# H-mostik2.net
KiCad netlist of a schematic drawn in Altium Designer
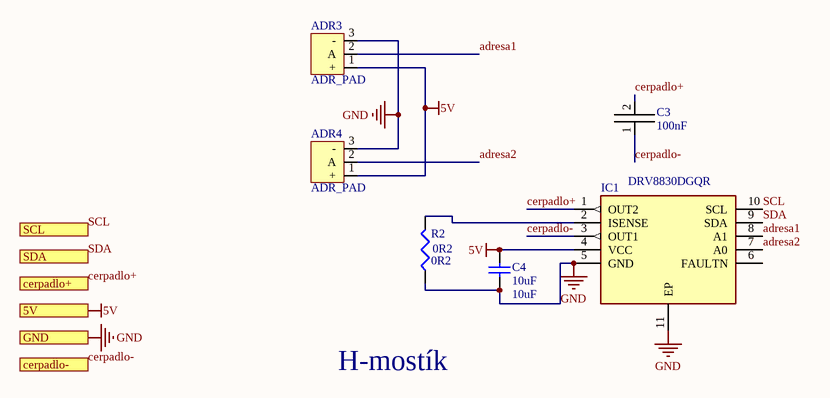
[diagram p0: H-mostik2.SchDoc]

(export (version "E")
  (design (tool "Eeschema 10.0.6"))
  (components
    (comp (ref "ADR3")
      (value "ADR_PAD")
      (footprint "SOLDER_PAD")
      (description "ADR PAD 3 PIN")
      (libsource (lib "SCH_Aquatec") (part "ADR_PAD"))
    )
    (comp (ref "ADR4")
      (value "ADR_PAD")
      (footprint "SOLDER_PAD")
      (description "ADR PAD 3 PIN")
      (libsource (lib "SCH_Aquatec") (part "ADR_PAD"))
    )
    (comp (ref "C3") (value "100nF") (footprint "Capacitor") (libsource (lib "SchematicLib_JP") (part "Cap")))
    (comp (ref "C4")
      (value "10uF")
      (footprint "C2512")
      (description "Capacitor (Semiconductor SIM Model)")
      (fields (field (name "ALTIUM_VALUE") "10uF") (field (name "PUBLISHER") "Altium Limited"))
      (libsource (lib "Miscellaneous Devices") (part "Cap Semi"))
    )
    (comp (ref "IC1")
      (value "DRV8830DGQR")
      (footprint "SOP50P490X110-11N")
      (description "Integrated Circuit")
      (fields (field (name "MOUSER PART NUMBER") "595-DRV8830DGQR") (field (name "RS PART NUMBER") "1626149"))
      (libsource (lib "*") (part "DRV8830DGQR"))
    )
    (comp (ref "R2")
      (value "0R2")
      (footprint "J1-0603")
      (description "Resistor")
      (fields (field (name "ALTIUM_VALUE") "0R2") (field (name "PUBLISHER") "Altium Limited"))
      (libsource (lib "Miscellaneous Devices") (part "Res3"))
    )
  )
  (nets
    (net (code "1") (name "/SCL") (class "Default")
      (node (ref "IC1") (pin "10") (pinfunction "SCL_10") (pintype "passive"))
    )
    (net (code "2") (name "/SDA") (class "Default")
      (node (ref "IC1") (pin "9") (pinfunction "SDA_9") (pintype "passive"))
    )
    (net (code "3") (name "/adresa1") (class "Default")
      (node (ref "ADR3") (pin "2") (pinfunction "A_2") (pintype "passive"))
      (node (ref "IC1") (pin "8") (pinfunction "A1_8") (pintype "passive"))
    )
    (net (code "4") (name "/adresa2") (class "Default")
      (node (ref "ADR4") (pin "2") (pinfunction "A_2") (pintype "passive"))
      (node (ref "IC1") (pin "7") (pinfunction "A0_7") (pintype "passive"))
    )
    (net (code "5") (name "/cerpadlo+") (class "Default")
      (node (ref "C3") (pin "2") (pinfunction "2_2") (pintype "passive"))
      (node (ref "IC1") (pin "1") (pinfunction "OUT2_1") (pintype "output"))
    )
    (net (code "6") (name "/cerpadlo-") (class "Default")
      (node (ref "C3") (pin "1") (pinfunction "1_1") (pintype "passive"))
      (node (ref "IC1") (pin "3") (pinfunction "OUT1_3") (pintype "output"))
    )
    (net (code "7") (name "5V") (class "Default")
      (node (ref "ADR3") (pin "1") (pinfunction "+_1") (pintype "passive"))
      (node (ref "ADR4") (pin "1") (pinfunction "+_1") (pintype "passive"))
      (node (ref "C4") (pin "2") (pinfunction "2_2") (pintype "passive"))
      (node (ref "IC1") (pin "4") (pinfunction "VCC_4") (pintype "power_in"))
    )
    (net (code "8") (name "GND") (class "Default")
      (node (ref "ADR3") (pin "3") (pinfunction "-_3") (pintype "passive"))
      (node (ref "ADR4") (pin "3") (pinfunction "-_3") (pintype "passive"))
      (node (ref "C4") (pin "1") (pinfunction "1_1") (pintype "passive"))
      (node (ref "IC1") (pin "11") (pinfunction "EP_11") (pintype "passive"))
      (node (ref "IC1") (pin "5") (pinfunction "GND_5") (pintype "power_in"))
      (node (ref "R2") (pin "1") (pinfunction "1_1") (pintype "passive"))
    )
    (net (code "9") (name "Net-(IC1-ISENSE)") (class "Default")
      (node (ref "IC1") (pin "2") (pinfunction "ISENSE_2") (pintype "passive"))
      (node (ref "R2") (pin "2") (pinfunction "2_2") (pintype "passive"))
    )
    (net (code "10") (name "unconnected-(IC1-FAULTN-Pad6)") (class "Default")
      (node (ref "IC1") (pin "6") (pinfunction "FAULTN_6") (pintype "passive"))
    )
  )
)
